# 005743-001.net
KiCad netlist of a schematic drawn in EAGLE
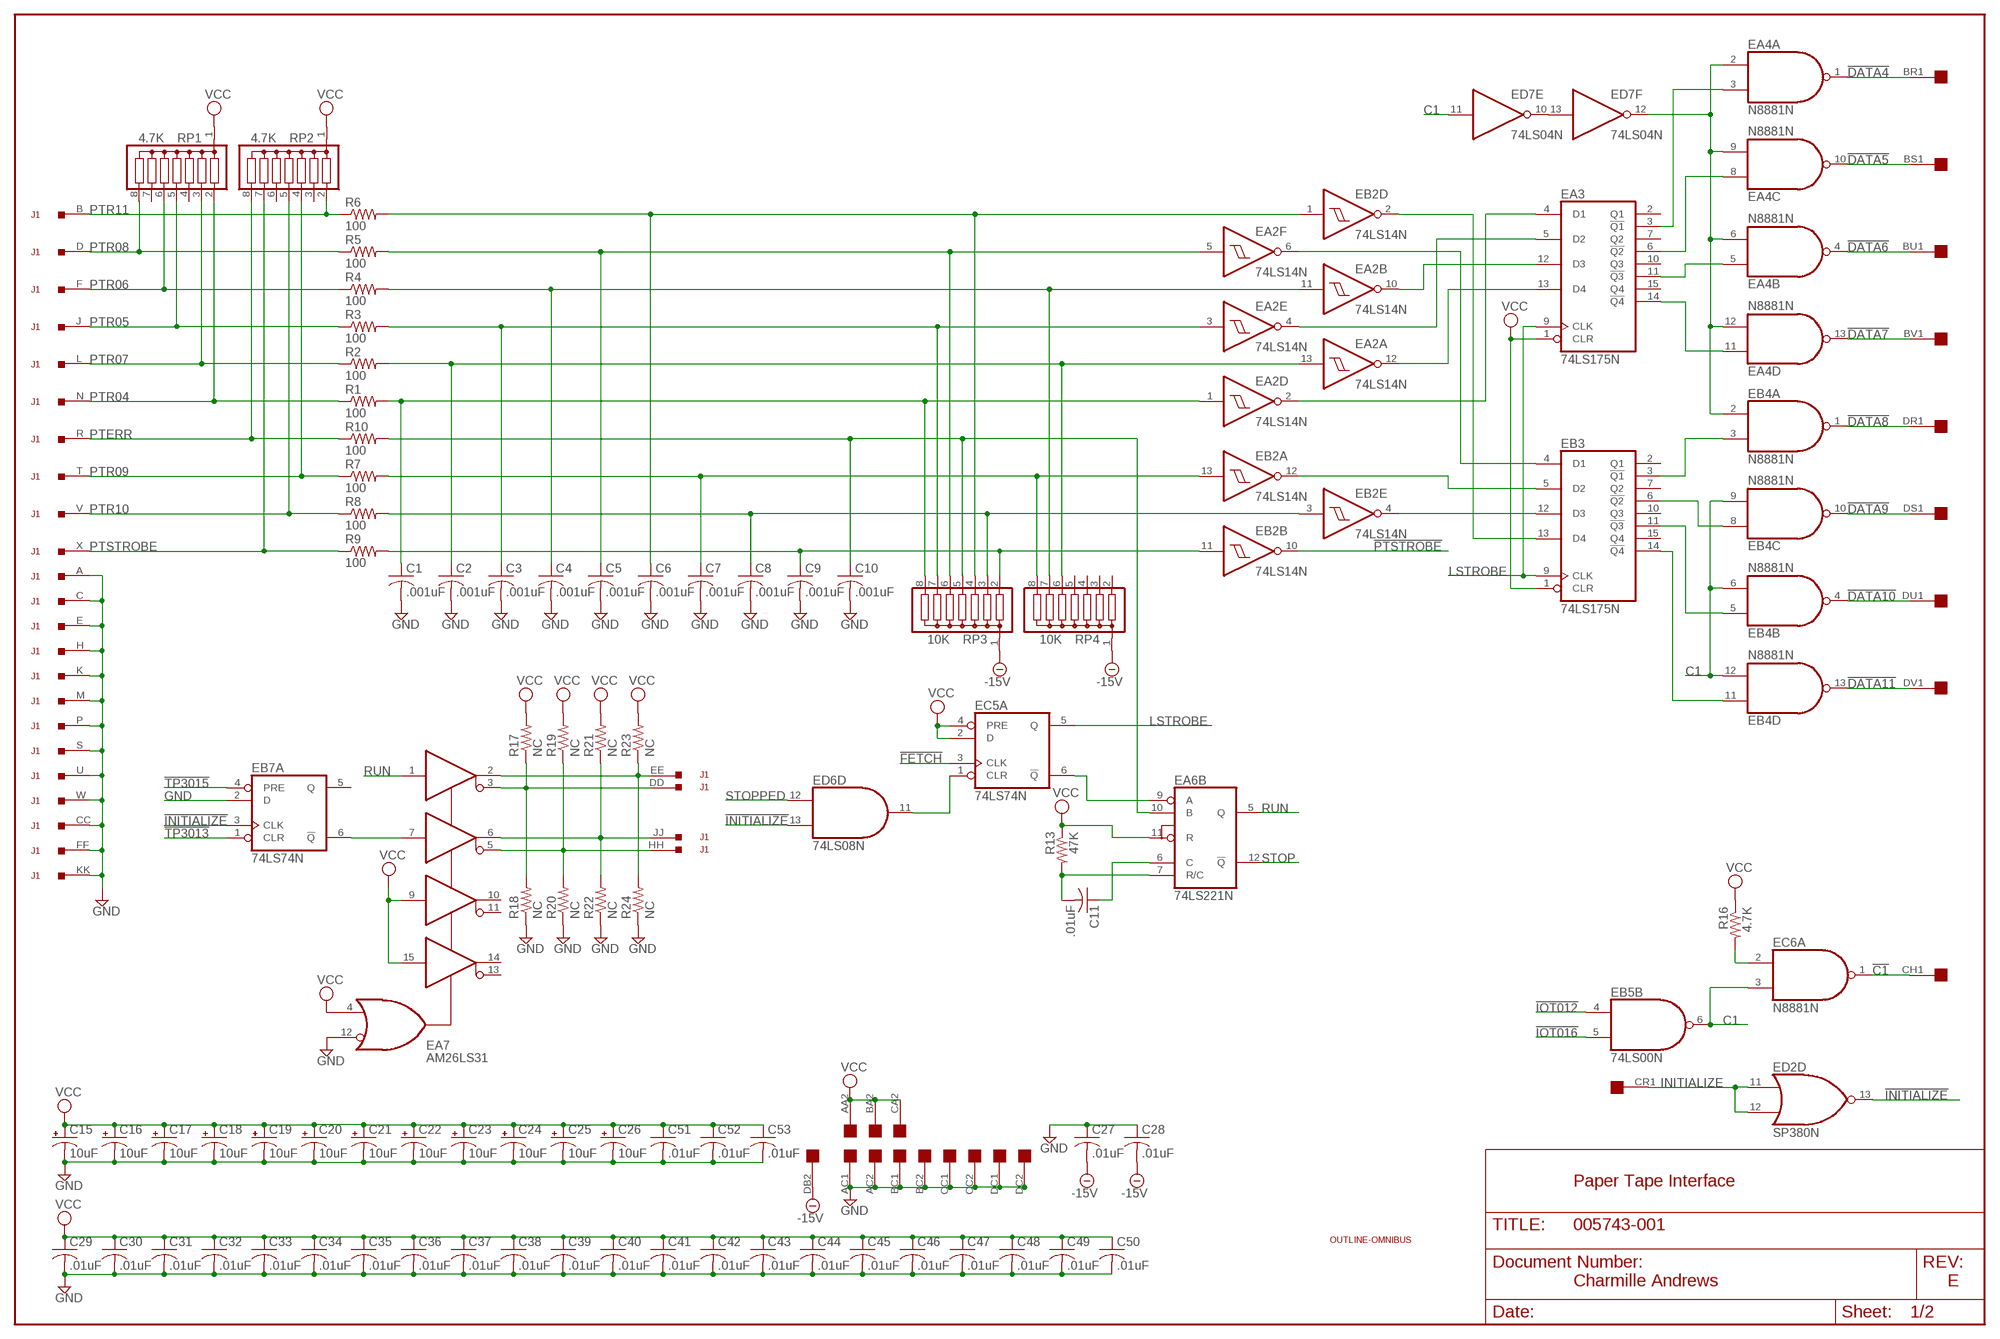
[diagram p0: schematic, sheet 1]
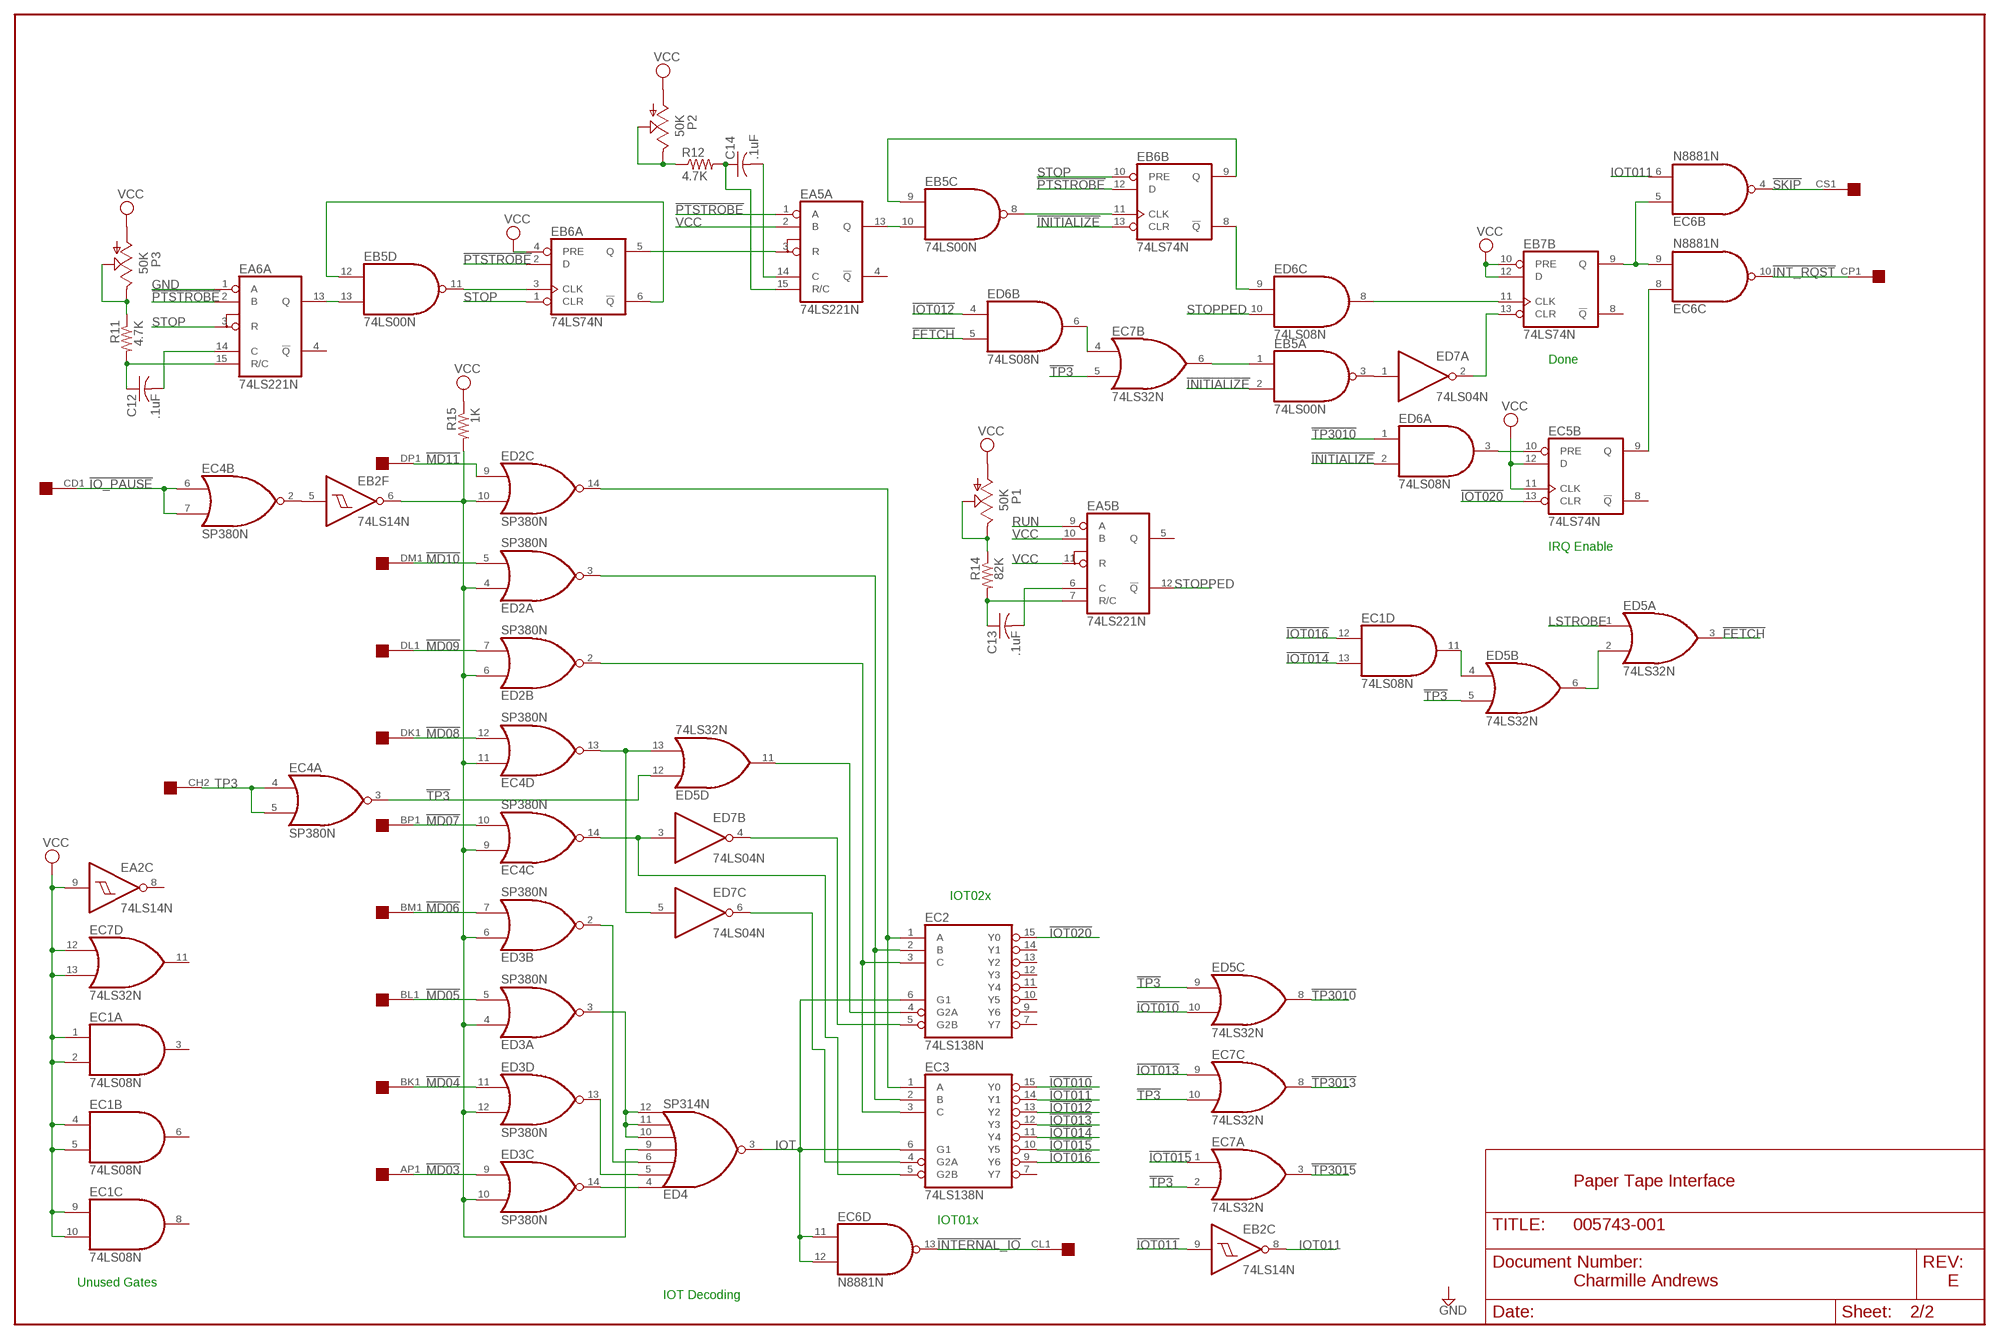
[diagram p1: schematic, sheet 2]

(export (version "E")
  (design (tool "Eeschema 10.0.6"))
  (components
    (comp (ref "C12")
      (value ".1uF")
      (footprint "eagle-import:C150-054X183")
      (libsource (lib "eagle-import") (part "C-US150-054X183"))
    )
    (comp (ref "C13")
      (value ".1uF")
      (footprint "eagle-import:C150-054X183")
      (libsource (lib "eagle-import") (part "C-US150-054X183"))
    )
    (comp (ref "C14")
      (value ".1uF")
      (footprint "eagle-import:C150-054X183")
      (libsource (lib "eagle-import") (part "C-US150-054X183"))
    )
    (comp (ref "EA2")
      (value "74LS14N")
      (footprint "eagle-import:DIL14")
      (libsource (lib "eagle-import") (part "7414NLS"))
    )
    (comp (ref "EA5")
      (value "74LS221N")
      (footprint "eagle-import:DIL16")
      (libsource (lib "eagle-import") (part "74221NLS"))
    )
    (comp (ref "EA6")
      (value "74LS221N")
      (footprint "eagle-import:DIL16")
      (libsource (lib "eagle-import") (part "74221NLS"))
    )
    (comp (ref "EB2")
      (value "74LS14N")
      (footprint "eagle-import:DIL14")
      (libsource (lib "eagle-import") (part "7414NLS"))
    )
    (comp (ref "EB5")
      (value "74LS00N")
      (footprint "eagle-import:DIL14")
      (libsource (lib "eagle-import") (part "7400NLS"))
    )
    (comp (ref "EB6")
      (value "74LS74N")
      (footprint "eagle-import:DIL14")
      (libsource (lib "eagle-import") (part "7474NLS"))
    )
    (comp (ref "EB7")
      (value "74LS74N")
      (footprint "eagle-import:DIL14")
      (libsource (lib "eagle-import") (part "7474NLS"))
    )
    (comp (ref "EC1")
      (value "74LS08N")
      (footprint "eagle-import:DIL14")
      (libsource (lib "eagle-import") (part "7408NLS"))
    )
    (comp (ref "EC2")
      (value "74LS138N")
      (footprint "eagle-import:DIL16")
      (libsource (lib "eagle-import") (part "74138NLS"))
    )
    (comp (ref "EC3")
      (value "74LS138N")
      (footprint "eagle-import:DIL16")
      (libsource (lib "eagle-import") (part "74138NLS"))
    )
    (comp (ref "EC4")
      (value "SP380N")
      (footprint "eagle-import:DIL14")
      (libsource (lib "eagle-import") (part "SP380N"))
    )
    (comp (ref "EC5")
      (value "74LS74N")
      (footprint "eagle-import:DIL14")
      (libsource (lib "eagle-import") (part "7474NLS"))
    )
    (comp (ref "EC6")
      (value "N8881N")
      (footprint "eagle-import:DIL14")
      (libsource (lib "eagle-import") (part "N8881N"))
    )
    (comp (ref "EC7")
      (value "74LS32N")
      (footprint "eagle-import:DIL14")
      (libsource (lib "eagle-import") (part "7432NLS"))
    )
    (comp (ref "ED2")
      (value "SP380N")
      (footprint "eagle-import:DIL14")
      (libsource (lib "eagle-import") (part "SP380N"))
    )
    (comp (ref "ED3")
      (value "SP380N")
      (footprint "eagle-import:DIL14")
      (libsource (lib "eagle-import") (part "SP380N"))
    )
    (comp (ref "ED4")
      (value "SP314N")
      (footprint "eagle-import:DIL14")
      (libsource (lib "eagle-import") (part "SP314N"))
    )
    (comp (ref "ED5")
      (value "74LS32N")
      (footprint "eagle-import:DIL14")
      (libsource (lib "eagle-import") (part "7432NLS"))
    )
    (comp (ref "ED6")
      (value "74LS08N")
      (footprint "eagle-import:DIL14")
      (libsource (lib "eagle-import") (part "7408NLS"))
    )
    (comp (ref "ED7")
      (value "74LS04N")
      (footprint "eagle-import:DIL14")
      (libsource (lib "eagle-import") (part "7404NLS"))
    )
    (comp (ref "P1")
      (value "50K")
      (footprint "eagle-import:SP19L")
      (libsource (lib "eagle-import") (part "TRIM_US-S43P"))
    )
    (comp (ref "P2")
      (value "50K")
      (footprint "eagle-import:SP19L")
      (libsource (lib "eagle-import") (part "TRIM_US-S43P"))
    )
    (comp (ref "P3")
      (value "50K")
      (footprint "eagle-import:SP19L")
      (libsource (lib "eagle-import") (part "TRIM_US-S43P"))
    )
    (comp (ref "R11")
      (value "4.7K")
      (footprint "eagle-import:0207_12")
      (libsource (lib "eagle-import") (part "R-US_0207/12"))
    )
    (comp (ref "R12")
      (value "4.7K")
      (footprint "eagle-import:0207_12")
      (libsource (lib "eagle-import") (part "R-US_0207/12"))
    )
    (comp (ref "R14")
      (value "82K")
      (footprint "eagle-import:0207_12")
      (libsource (lib "eagle-import") (part "R-US_0207/12"))
    )
    (comp (ref "R15")
      (value "1K")
      (footprint "eagle-import:0207_12")
      (libsource (lib "eagle-import") (part "R-US_0207/12"))
    )
    (comp (ref "U$2")
      (value "QUAD")
      (footprint "eagle-import:EDGE-CON8")
      (libsource (lib "eagle-import") (part "QUAD"))
    )
    (comp (ref "C1")
      (value ".001uF")
      (footprint "eagle-import:C050-025X075")
      (libsource (lib "eagle-import") (part "C-US050-025X075"))
    )
    (comp (ref "C2")
      (value ".001uF")
      (footprint "eagle-import:C050-025X075")
      (libsource (lib "eagle-import") (part "C-US050-025X075"))
    )
    (comp (ref "C3")
      (value ".001uF")
      (footprint "eagle-import:C050-025X075")
      (libsource (lib "eagle-import") (part "C-US050-025X075"))
    )
    (comp (ref "C4")
      (value ".001uF")
      (footprint "eagle-import:C050-025X075")
      (libsource (lib "eagle-import") (part "C-US050-025X075"))
    )
    (comp (ref "C5")
      (value ".001uF")
      (footprint "eagle-import:C050-025X075")
      (libsource (lib "eagle-import") (part "C-US050-025X075"))
    )
    (comp (ref "C6")
      (value ".001uF")
      (footprint "eagle-import:C050-025X075")
      (libsource (lib "eagle-import") (part "C-US050-025X075"))
    )
    (comp (ref "C7")
      (value ".001uF")
      (footprint "eagle-import:C050-025X075")
      (libsource (lib "eagle-import") (part "C-US050-025X075"))
    )
    (comp (ref "C8")
      (value ".001uF")
      (footprint "eagle-import:C050-025X075")
      (libsource (lib "eagle-import") (part "C-US050-025X075"))
    )
    (comp (ref "C9")
      (value ".001uF")
      (footprint "eagle-import:C050-025X075")
      (libsource (lib "eagle-import") (part "C-US050-025X075"))
    )
    (comp (ref "C10")
      (value ".001uF")
      (footprint "eagle-import:C050-025X075")
      (libsource (lib "eagle-import") (part "C-US050-025X075"))
    )
    (comp (ref "C11")
      (value ".01uF")
      (footprint "eagle-import:C050-025X075")
      (libsource (lib "eagle-import") (part "C-US050-025X075"))
    )
    (comp (ref "C15")
      (value "10uF")
      (footprint "eagle-import:E15-5")
      (libsource (lib "eagle-import") (part "CPOL-USE15-5AXIAL"))
    )
    (comp (ref "C16")
      (value "10uF")
      (footprint "eagle-import:E15-5")
      (libsource (lib "eagle-import") (part "rcl_CPOL-USE15-5AXIAL"))
    )
    (comp (ref "C17")
      (value "10uF")
      (footprint "eagle-import:E15-5")
      (libsource (lib "eagle-import") (part "rcl_CPOL-USE15-5AXIAL"))
    )
    (comp (ref "C18")
      (value "10uF")
      (footprint "eagle-import:E15-5")
      (libsource (lib "eagle-import") (part "CPOL-USE15-5AXIAL"))
    )
    (comp (ref "C19")
      (value "10uF")
      (footprint "eagle-import:E15-5")
      (libsource (lib "eagle-import") (part "rcl_CPOL-USE15-5AXIAL"))
    )
    (comp (ref "C20")
      (value "10uF")
      (footprint "eagle-import:E15-5")
      (libsource (lib "eagle-import") (part "CPOL-USE15-5AXIAL"))
    )
    (comp (ref "C21")
      (value "10uF")
      (footprint "eagle-import:E15-5")
      (libsource (lib "eagle-import") (part "CPOL-USE15-5AXIAL"))
    )
    (comp (ref "C22")
      (value "10uF")
      (footprint "eagle-import:E15-5")
      (libsource (lib "eagle-import") (part "CPOL-USE15-5AXIAL"))
    )
    (comp (ref "C23")
      (value "10uF")
      (footprint "eagle-import:E15-5")
      (libsource (lib "eagle-import") (part "rcl_CPOL-USE15-5AXIAL"))
    )
    (comp (ref "C24")
      (value "10uF")
      (footprint "eagle-import:E15-5")
      (libsource (lib "eagle-import") (part "rcl_CPOL-USE15-5AXIAL"))
    )
    (comp (ref "C25")
      (value "10uF")
      (footprint "eagle-import:E15-5")
      (libsource (lib "eagle-import") (part "rcl_CPOL-USE15-5AXIAL"))
    )
    (comp (ref "C26")
      (value "10uF")
      (footprint "eagle-import:E15-5")
      (libsource (lib "eagle-import") (part "rcl_CPOL-USE15-5AXIAL"))
    )
    (comp (ref "C27")
      (value ".01uF")
      (footprint "eagle-import:C050-025X075")
      (libsource (lib "eagle-import") (part "C-US050-025X075"))
    )
    (comp (ref "C28")
      (value ".01uF")
      (footprint "eagle-import:C050-025X075")
      (libsource (lib "eagle-import") (part "C-US050-025X075"))
    )
    (comp (ref "C29")
      (value ".01uF")
      (footprint "eagle-import:C050-025X075")
      (libsource (lib "eagle-import") (part "C-US050-025X075"))
    )
    (comp (ref "C30")
      (value ".01uF")
      (footprint "eagle-import:C050-025X075")
      (libsource (lib "eagle-import") (part "C-US050-025X075"))
    )
    (comp (ref "C31")
      (value ".01uF")
      (footprint "eagle-import:C050-025X075")
      (libsource (lib "eagle-import") (part "C-US050-025X075"))
    )
    (comp (ref "C32")
      (value ".01uF")
      (footprint "eagle-import:C050-025X075")
      (libsource (lib "eagle-import") (part "C-US050-025X075"))
    )
    (comp (ref "C33")
      (value ".01uF")
      (footprint "eagle-import:C050-025X075")
      (libsource (lib "eagle-import") (part "C-US050-025X075"))
    )
    (comp (ref "C34")
      (value ".01uF")
      (footprint "eagle-import:C050-025X075")
      (libsource (lib "eagle-import") (part "C-US050-025X075"))
    )
    (comp (ref "C35")
      (value ".01uF")
      (footprint "eagle-import:C050-025X075")
      (libsource (lib "eagle-import") (part "C-US050-025X075"))
    )
    (comp (ref "C36")
      (value ".01uF")
      (footprint "eagle-import:C050-025X075")
      (libsource (lib "eagle-import") (part "C-US050-025X075"))
    )
    (comp (ref "C37")
      (value ".01uF")
      (footprint "eagle-import:C050-025X075")
      (libsource (lib "eagle-import") (part "C-US050-025X075"))
    )
    (comp (ref "C38")
      (value ".01uF")
      (footprint "eagle-import:C050-025X075")
      (libsource (lib "eagle-import") (part "C-US050-025X075"))
    )
    (comp (ref "C39")
      (value ".01uF")
      (footprint "eagle-import:C050-025X075")
      (libsource (lib "eagle-import") (part "C-US050-025X075"))
    )
    (comp (ref "C40")
      (value ".01uF")
      (footprint "eagle-import:C050-025X075")
      (libsource (lib "eagle-import") (part "C-US050-025X075"))
    )
    (comp (ref "C41")
      (value ".01uF")
      (footprint "eagle-import:C050-025X075")
      (libsource (lib "eagle-import") (part "C-US050-025X075"))
    )
    (comp (ref "C42")
      (value ".01uF")
      (footprint "eagle-import:C050-025X075")
      (libsource (lib "eagle-import") (part "C-US050-025X075"))
    )
    (comp (ref "C43")
      (value ".01uF")
      (footprint "eagle-import:C050-025X075")
      (libsource (lib "eagle-import") (part "C-US050-025X075"))
    )
    (comp (ref "C44")
      (value ".01uF")
      (footprint "eagle-import:C050-025X075")
      (libsource (lib "eagle-import") (part "C-US050-025X075"))
    )
    (comp (ref "C45")
      (value ".01uF")
      (footprint "eagle-import:C050-025X075")
      (libsource (lib "eagle-import") (part "C-US050-025X075"))
    )
    (comp (ref "C46")
      (value ".01uF")
      (footprint "eagle-import:C050-025X075")
      (libsource (lib "eagle-import") (part "C-US050-025X075"))
    )
    (comp (ref "C47")
      (value ".01uF")
      (footprint "eagle-import:C050-025X075")
      (libsource (lib "eagle-import") (part "C-US050-025X075"))
    )
    (comp (ref "C48")
      (value ".01uF")
      (footprint "eagle-import:C050-025X075")
      (libsource (lib "eagle-import") (part "C-US050-025X075"))
    )
    (comp (ref "C49")
      (value ".01uF")
      (footprint "eagle-import:C050-025X075")
      (libsource (lib "eagle-import") (part "C-US050-025X075"))
    )
    (comp (ref "C50")
      (value ".01uF")
      (footprint "eagle-import:C050-025X075")
      (libsource (lib "eagle-import") (part "C-US050-025X075"))
    )
    (comp (ref "C51")
      (value ".01uF")
      (footprint "eagle-import:C050-025X075")
      (libsource (lib "eagle-import") (part "C-US050-025X075"))
    )
    (comp (ref "C52")
      (value ".01uF")
      (footprint "eagle-import:C050-025X075")
      (libsource (lib "eagle-import") (part "C-US050-025X075"))
    )
    (comp (ref "C53")
      (value ".01uF")
      (footprint "eagle-import:C050-025X075")
      (libsource (lib "eagle-import") (part "C-US050-025X075"))
    )
    (comp (ref "EA3")
      (value "74LS175N")
      (footprint "eagle-import:DIL16")
      (libsource (lib "eagle-import") (part "74175NLS"))
    )
    (comp (ref "EA4")
      (value "N8881N")
      (footprint "eagle-import:DIL14")
      (libsource (lib "eagle-import") (part "N8881N"))
    )
    (comp (ref "EA7")
      (value "AM26LS31")
      (footprint "eagle-import:DIL16")
      (libsource (lib "eagle-import") (part "AM26LS31"))
    )
    (comp (ref "EB3")
      (value "74LS175N")
      (footprint "eagle-import:DIL16")
      (libsource (lib "eagle-import") (part "74175NLS"))
    )
    (comp (ref "EB4")
      (value "N8881N")
      (footprint "eagle-import:DIL14")
      (libsource (lib "eagle-import") (part "N8881N"))
    )
    (comp (ref "J1")
      (value "DEC40PINSH")
      (footprint "eagle-import:DEC40PINH")
      (libsource (lib "eagle-import") (part "DEC40PINSH"))
    )
    (comp (ref "R1")
      (value "100")
      (footprint "eagle-import:0207_12")
      (libsource (lib "eagle-import") (part "R-US_0207/12"))
    )
    (comp (ref "R2")
      (value "100")
      (footprint "eagle-import:0207_12")
      (libsource (lib "eagle-import") (part "R-US_0207/12"))
    )
    (comp (ref "R3")
      (value "100")
      (footprint "eagle-import:0207_12")
      (libsource (lib "eagle-import") (part "R-US_0207/12"))
    )
    (comp (ref "R4")
      (value "100")
      (footprint "eagle-import:0207_12")
      (libsource (lib "eagle-import") (part "R-US_0207/12"))
    )
    (comp (ref "R5")
      (value "100")
      (footprint "eagle-import:0207_12")
      (libsource (lib "eagle-import") (part "R-US_0207/12"))
    )
    (comp (ref "R6")
      (value "100")
      (footprint "eagle-import:0207_12")
      (libsource (lib "eagle-import") (part "R-US_0207/12"))
    )
    (comp (ref "R7")
      (value "100")
      (footprint "eagle-import:0207_12")
      (libsource (lib "eagle-import") (part "R-US_0207/12"))
    )
    (comp (ref "R8")
      (value "100")
      (footprint "eagle-import:0207_12")
      (libsource (lib "eagle-import") (part "R-US_0207/12"))
    )
    (comp (ref "R9")
      (value "100")
      (footprint "eagle-import:0207_12")
      (libsource (lib "eagle-import") (part "R-US_0207/12"))
    )
    (comp (ref "R10")
      (value "100")
      (footprint "eagle-import:0207_12")
      (libsource (lib "eagle-import") (part "R-US_0207/12"))
    )
    (comp (ref "R13")
      (value "47K")
      (footprint "eagle-import:0207_12")
      (libsource (lib "eagle-import") (part "R-US_0207/12"))
    )
    (comp (ref "R16")
      (value "4.7K")
      (footprint "eagle-import:0207_12")
      (libsource (lib "eagle-import") (part "R-US_0207/12"))
    )
    (comp (ref "R17")
      (value "NC")
      (footprint "eagle-import:0207_12")
      (libsource (lib "eagle-import") (part "R-US_0207/12"))
    )
    (comp (ref "R18")
      (value "NC")
      (footprint "eagle-import:0207_12")
      (libsource (lib "eagle-import") (part "R-US_0207/12"))
    )
    (comp (ref "R19")
      (value "NC")
      (footprint "eagle-import:0207_12")
      (libsource (lib "eagle-import") (part "R-US_0207/12"))
    )
    (comp (ref "R20")
      (value "NC")
      (footprint "eagle-import:0207_12")
      (libsource (lib "eagle-import") (part "R-US_0207/12"))
    )
    (comp (ref "R21")
      (value "NC")
      (footprint "eagle-import:0207_12")
      (libsource (lib "eagle-import") (part "R-US_0207/12"))
    )
    (comp (ref "R22")
      (value "NC")
      (footprint "eagle-import:0207_12")
      (libsource (lib "eagle-import") (part "R-US_0207/12"))
    )
    (comp (ref "R23")
      (value "NC")
      (footprint "eagle-import:0207_12")
      (libsource (lib "eagle-import") (part "R-US_0207/12"))
    )
    (comp (ref "R24")
      (value "NC")
      (footprint "eagle-import:0207_12")
      (libsource (lib "eagle-import") (part "R-US_0207/12"))
    )
    (comp (ref "RP1")
      (value "4.7K")
      (footprint "eagle-import:SIL8")
      (libsource (lib "eagle-import") (part "G07R"))
    )
    (comp (ref "RP2")
      (value "4.7K")
      (footprint "eagle-import:SIL8")
      (libsource (lib "eagle-import") (part "G07R"))
    )
    (comp (ref "RP3")
      (value "10K")
      (footprint "eagle-import:SIL8")
      (libsource (lib "eagle-import") (part "G07R"))
    )
    (comp (ref "RP4")
      (value "10K")
      (footprint "eagle-import:SIL8")
      (libsource (lib "eagle-import") (part "G07R"))
    )
    (comp (ref "U$1")
      (value "OUTLINE-OMNIBUS")
      (footprint "eagle-import:OMNIBUS")
      (libsource (lib "eagle-import") (part "OUTLINE-OMNIBUS"))
    )
  )
  (nets
    (net (code "1") (name "-15V") (class "Default")
      (node (ref "C27") (pin "2") (pinfunction "2_2") (pintype "passive"))
      (node (ref "C28") (pin "2") (pinfunction "2_2") (pintype "passive"))
      (node (ref "RP3") (pin "1") (pinfunction "1_1") (pintype "passive"))
      (node (ref "RP4") (pin "1") (pinfunction "1_1") (pintype "passive"))
      (node (ref "U$2") (pin "DB2") (pinfunction "1_DB2") (pintype "bidirectional"))
    )
    (net (code "2") (name "C1") (class "Default")
      (node (ref "EB4") (pin "12") (pinfunction "I1_12") (pintype "input"))
      (node (ref "EB4") (pin "6") (pinfunction "I1_6") (pintype "input"))
      (node (ref "EB4") (pin "9") (pinfunction "I1_9") (pintype "input"))
      (node (ref "EB5") (pin "6") (pinfunction "O_6") (pintype "output"))
      (node (ref "EC6") (pin "3") (pinfunction "I1_3") (pintype "input"))
      (node (ref "ED7") (pin "11") (pinfunction "I_11") (pintype "input"))
    )
    (net (code "3") (name "GND") (class "Default")
      (node (ref "C1") (pin "2") (pinfunction "2_2") (pintype "passive"))
      (node (ref "C10") (pin "2") (pinfunction "2_2") (pintype "passive"))
      (node (ref "C15") (pin "-") (pinfunction "-_-") (pintype "passive"))
      (node (ref "C16") (pin "-") (pinfunction "-_-") (pintype "passive"))
      (node (ref "C17") (pin "-") (pinfunction "-_-") (pintype "passive"))
      (node (ref "C18") (pin "-") (pinfunction "-_-") (pintype "passive"))
      (node (ref "C19") (pin "-") (pinfunction "-_-") (pintype "passive"))
      (node (ref "C2") (pin "2") (pinfunction "2_2") (pintype "passive"))
      (node (ref "C20") (pin "-") (pinfunction "-_-") (pintype "passive"))
      (node (ref "C21") (pin "-") (pinfunction "-_-") (pintype "passive"))
      (node (ref "C22") (pin "-") (pinfunction "-_-") (pintype "passive"))
      (node (ref "C23") (pin "-") (pinfunction "-_-") (pintype "passive"))
      (node (ref "C24") (pin "-") (pinfunction "-_-") (pintype "passive"))
      (node (ref "C25") (pin "-") (pinfunction "-_-") (pintype "passive"))
      (node (ref "C26") (pin "-") (pinfunction "-_-") (pintype "passive"))
      (node (ref "C27") (pin "1") (pinfunction "1_1") (pintype "passive"))
      (node (ref "C28") (pin "1") (pinfunction "1_1") (pintype "passive"))
      (node (ref "C29") (pin "2") (pinfunction "2_2") (pintype "passive"))
      (node (ref "C3") (pin "2") (pinfunction "2_2") (pintype "passive"))
      (node (ref "C30") (pin "2") (pinfunction "2_2") (pintype "passive"))
      (node (ref "C31") (pin "2") (pinfunction "2_2") (pintype "passive"))
      (node (ref "C32") (pin "2") (pinfunction "2_2") (pintype "passive"))
      (node (ref "C33") (pin "2") (pinfunction "2_2") (pintype "passive"))
      (node (ref "C34") (pin "2") (pinfunction "2_2") (pintype "passive"))
      (node (ref "C35") (pin "2") (pinfunction "2_2") (pintype "passive"))
      (node (ref "C36") (pin "2") (pinfunction "2_2") (pintype "passive"))
      (node (ref "C37") (pin "2") (pinfunction "2_2") (pintype "passive"))
      (node (ref "C38") (pin "2") (pinfunction "2_2") (pintype "passive"))
      (node (ref "C39") (pin "2") (pinfunction "2_2") (pintype "passive"))
      (node (ref "C4") (pin "2") (pinfunction "2_2") (pintype "passive"))
      (node (ref "C40") (pin "2") (pinfunction "2_2") (pintype "passive"))
      (node (ref "C41") (pin "2") (pinfunction "2_2") (pintype "passive"))
      (node (ref "C42") (pin "2") (pinfunction "2_2") (pintype "passive"))
      (node (ref "C43") (pin "2") (pinfunction "2_2") (pintype "passive"))
      (node (ref "C44") (pin "2") (pinfunction "2_2") (pintype "passive"))
      (node (ref "C45") (pin "2") (pinfunction "2_2") (pintype "passive"))
      (node (ref "C46") (pin "2") (pinfunction "2_2") (pintype "passive"))
      (node (ref "C47") (pin "2") (pinfunction "2_2") (pintype "passive"))
      (node (ref "C48") (pin "2") (pinfunction "2_2") (pintype "passive"))
      (node (ref "C49") (pin "2") (pinfunction "2_2") (pintype "passive"))
      (node (ref "C5") (pin "2") (pinfunction "2_2") (pintype "passive"))
      (node (ref "C50") (pin "2") (pinfunction "2_2") (pintype "passive"))
      (node (ref "C51") (pin "2") (pinfunction "2_2") (pintype "passive"))
      (node (ref "C52") (pin "2") (pinfunction "2_2") (pintype "passive"))
      (node (ref "C53") (pin "2") (pinfunction "2_2") (pintype "passive"))
      (node (ref "C6") (pin "2") (pinfunction "2_2") (pintype "passive"))
      (node (ref "C7") (pin "2") (pinfunction "2_2") (pintype "passive"))
      (node (ref "C8") (pin "2") (pinfunction "2_2") (pintype "passive"))
      (node (ref "C9") (pin "2") (pinfunction "2_2") (pintype "passive"))
      (node (ref "EA6") (pin "1") (pinfunction "A_1") (pintype "input"))
      (node (ref "EA7") (pin "12") (pinfunction "~{G}_12") (pintype "input"))
      (node (ref "EB7") (pin "2") (pinfunction "D_2") (pintype "input"))
      (node (ref "J1") (pin "A") (pinfunction "P$2_A") (pintype "passive"))
      (node (ref "J1") (pin "C") (pinfunction "P$2_C") (pintype "passive"))
      (node (ref "J1") (pin "CC") (pinfunction "P$2_CC") (pintype "passive"))
      (node (ref "J1") (pin "E") (pinfunction "P$2_E") (pintype "passive"))
      (node (ref "J1") (pin "FF") (pinfunction "P$2_FF") (pintype "passive"))
      (node (ref "J1") (pin "H") (pinfunction "P$2_H") (pintype "passive"))
      (node (ref "J1") (pin "K") (pinfunction "P$2_K") (pintype "passive"))
      (node (ref "J1") (pin "KK") (pinfunction "P$2_KK") (pintype "passive"))
      (node (ref "J1") (pin "M") (pinfunction "P$2_M") (pintype "passive"))
      (node (ref "J1") (pin "P") (pinfunction "P$2_P") (pintype "passive"))
      (node (ref "J1") (pin "S") (pinfunction "P$2_S") (pintype "passive"))
      (node (ref "J1") (pin "U") (pinfunction "P$2_U") (pintype "passive"))
      (node (ref "J1") (pin "W") (pinfunction "P$2_W") (pintype "passive"))
      (node (ref "R18") (pin "1") (pinfunction "1_1") (pintype "passive"))
      (node (ref "R20") (pin "1") (pinfunction "1_1") (pintype "passive"))
      (node (ref "R22") (pin "1") (pinfunction "1_1") (pintype "passive"))
      (node (ref "R24") (pin "1") (pinfunction "1_1") (pintype "passive"))
      (node (ref "U$2") (pin "AC1") (pinfunction "1_AC1") (pintype "bidirectional"))
      (node (ref "U$2") (pin "AC2") (pinfunction "1_AC2") (pintype "bidirectional"))
      (node (ref "U$2") (pin "BC1") (pinfunction "1_BC1") (pintype "bidirectional"))
      (node (ref "U$2") (pin "BC2") (pinfunction "1_BC2") (pintype "bidirectional"))
      (node (ref "U$2") (pin "CC1") (pinfunction "1_CC1") (pintype "bidirectional"))
      (node (ref "U$2") (pin "CC2") (pinfunction "1_CC2") (pintype "bidirectional"))
      (node (ref "U$2") (pin "DC1") (pinfunction "1_DC1") (pintype "bidirectional"))
      (node (ref "U$2") (pin "DC2") (pinfunction "1_DC2") (pintype "bidirectional"))
    )
    (net (code "4") (name "INITIALIZE") (class "Default")
      (node (ref "ED2") (pin "11") (pinfunction "I0_11") (pintype "input"))
      (node (ref "ED2") (pin "12") (pinfunction "I1_12") (pintype "input"))
      (node (ref "U$2") (pin "CR1") (pinfunction "1_CR1") (pintype "bidirectional"))
    )
    (net (code "5") (name "IOT") (class "Default")
      (node (ref "EC2") (pin "6") (pinfunction "G1_6") (pintype "input"))
      (node (ref "EC3") (pin "6") (pinfunction "G1_6") (pintype "input"))
      (node (ref "EC6") (pin "11") (pinfunction "I0_11") (pintype "input"))
      (node (ref "EC6") (pin "12") (pinfunction "I1_12") (pintype "input"))
      (node (ref "ED4") (pin "3") (pinfunction "O_3") (pintype "output"))
    )
    (net (code "6") (name "IOT011") (class "Default")
      (node (ref "EB2") (pin "8") (pinfunction "O_8") (pintype "output"))
      (node (ref "EC6") (pin "6") (pinfunction "I1_6") (pintype "input"))
    )
    (net (code "7") (name "LSTROBE") (class "Default")
      (node (ref "EA3") (pin "9") (pinfunction "CLK_9") (pintype "input"))
      (node (ref "EB3") (pin "9") (pinfunction "CLK_9") (pintype "input"))
      (node (ref "EC5") (pin "5") (pinfunction "Q_5") (pintype "output"))
      (node (ref "ED5") (pin "1") (pinfunction "I0_1") (pintype "input"))
    )
    (net (code "8") (name "Net-(EA2A-I)") (class "Default")
      (node (ref "C2") (pin "1") (pinfunction "1_1") (pintype "passive"))
      (node (ref "EA2") (pin "13") (pinfunction "I_13") (pintype "input"))
      (node (ref "R2") (pin "2") (pinfunction "2_2") (pintype "passive"))
      (node (ref "RP4") (pin "6") (pinfunction "6_6") (pintype "passive"))
    )
    (net (code "9") (name "Net-(EA2A-O)") (class "Default")
      (node (ref "EA2") (pin "12") (pinfunction "O_12") (pintype "output"))
      (node (ref "EA3") (pin "13") (pinfunction "D4_13") (pintype "input"))
    )
    (net (code "10") (name "Net-(EA2B-I)") (class "Default")
      (node (ref "C4") (pin "1") (pinfunction "1_1") (pintype "passive"))
      (node (ref "EA2") (pin "11") (pinfunction "I_11") (pintype "input"))
      (node (ref "R4") (pin "2") (pinfunction "2_2") (pintype "passive"))
      (node (ref "RP4") (pin "7") (pinfunction "7_7") (pintype "passive"))
    )
    (net (code "11") (name "Net-(EA2B-O)") (class "Default")
      (node (ref "EA2") (pin "10") (pinfunction "O_10") (pintype "output"))
      (node (ref "EA3") (pin "12") (pinfunction "D3_12") (pintype "input"))
    )
    (net (code "12") (name "Net-(EA2D-I)") (class "Default")
      (node (ref "C1") (pin "1") (pinfunction "1_1") (pintype "passive"))
      (node (ref "EA2") (pin "1") (pinfunction "I_1") (pintype "input"))
      (node (ref "R1") (pin "2") (pinfunction "2_2") (pintype "passive"))
      (node (ref "RP3") (pin "8") (pinfunction "8_8") (pintype "passive"))
    )
    (net (code "13") (name "Net-(EA2D-O)") (class "Default")
      (node (ref "EA2") (pin "2") (pinfunction "O_2") (pintype "output"))
      (node (ref "EA3") (pin "4") (pinfunction "D1_4") (pintype "input"))
    )
    (net (code "14") (name "Net-(EA2E-I)") (class "Default")
      (node (ref "C3") (pin "1") (pinfunction "1_1") (pintype "passive"))
      (node (ref "EA2") (pin "3") (pinfunction "I_3") (pintype "input"))
      (node (ref "R3") (pin "2") (pinfunction "2_2") (pintype "passive"))
      (node (ref "RP3") (pin "7") (pinfunction "7_7") (pintype "passive"))
    )
    (net (code "15") (name "Net-(EA2E-O)") (class "Default")
      (node (ref "EA2") (pin "4") (pinfunction "O_4") (pintype "output"))
      (node (ref "EA3") (pin "5") (pinfunction "D2_5") (pintype "input"))
    )
    (net (code "16") (name "Net-(EA2F-I)") (class "Default")
      (node (ref "C5") (pin "1") (pinfunction "1_1") (pintype "passive"))
      (node (ref "EA2") (pin "5") (pinfunction "I_5") (pintype "input"))
      (node (ref "R5") (pin "2") (pinfunction "2_2") (pintype "passive"))
      (node (ref "RP3") (pin "6") (pinfunction "6_6") (pintype "passive"))
    )
    (net (code "17") (name "Net-(EA2F-O)") (class "Default")
      (node (ref "EA2") (pin "6") (pinfunction "O_6") (pintype "output"))
      (node (ref "EB3") (pin "4") (pinfunction "D1_4") (pintype "input"))
    )
    (net (code "18") (name "Net-(EA3A-~{Q1})") (class "Default")
      (node (ref "EA3") (pin "3") (pinfunction "~{Q1}_3") (pintype "output"))
      (node (ref "EA4") (pin "3") (pinfunction "I1_3") (pintype "input"))
    )
    (net (code "19") (name "Net-(EA3A-~{Q2})") (class "Default")
      (node (ref "EA3") (pin "6") (pinfunction "~{Q2}_6") (pintype "output"))
      (node (ref "EA4") (pin "8") (pinfunction "I0_8") (pintype "input"))
    )
    (net (code "20") (name "Net-(EA3A-~{Q3})") (class "Default")
      (node (ref "EA3") (pin "11") (pinfunction "~{Q3}_11") (pintype "output"))
      (node (ref "EA4") (pin "5") (pinfunction "I0_5") (pintype "input"))
    )
    (net (code "21") (name "Net-(EA3A-~{Q4})") (class "Default")
      (node (ref "EA3") (pin "14") (pinfunction "~{Q4}_14") (pintype "output"))
      (node (ref "EA4") (pin "11") (pinfunction "I0_11") (pintype "input"))
    )
    (net (code "22") (name "Net-(EA4A-I0)") (class "Default")
      (node (ref "EA4") (pin "12") (pinfunction "I1_12") (pintype "input"))
      (node (ref "EA4") (pin "2") (pinfunction "I0_2") (pintype "input"))
      (node (ref "EA4") (pin "6") (pinfunction "I1_6") (pintype "input"))
      (node (ref "EA4") (pin "9") (pinfunction "I1_9") (pintype "input"))
      (node (ref "EB4") (pin "2") (pinfunction "I0_2") (pintype "input"))
      (node (ref "ED7") (pin "12") (pinfunction "O_12") (pintype "output"))
    )
    (net (code "23") (name "Net-(EA5A-C)") (class "Default")
      (node (ref "C14") (pin "2") (pinfunction "2_2") (pintype "passive"))
      (node (ref "EA5") (pin "14") (pinfunction "C_14") (pintype "input"))
    )
    (net (code "24") (name "Net-(EA5A-Q)") (class "Default")
      (node (ref "EA5") (pin "13") (pinfunction "Q_13") (pintype "output"))
      (node (ref "EB5") (pin "10") (pinfunction "I1_10") (pintype "input"))
    )
    (net (code "25") (name "Net-(EA5A-R)") (class "Default")
      (node (ref "EA5") (pin "3") (pinfunction "R_3") (pintype "input"))
      (node (ref "EB6") (pin "5") (pinfunction "Q_5") (pintype "output"))
    )
    (net (code "26") (name "Net-(EA5A-R{slash}C)") (class "Default")
      (node (ref "C14") (pin "1") (pinfunction "1_1") (pintype "passive"))
      (node (ref "EA5") (pin "15") (pinfunction "R/C_15") (pintype "input"))
      (node (ref "R12") (pin "2") (pinfunction "2_2") (pintype "passive"))
    )
    (net (code "27") (name "Net-(EA5B-C)") (class "Default")
      (node (ref "C13") (pin "2") (pinfunction "2_2") (pintype "passive"))
      (node (ref "EA5") (pin "6") (pinfunction "C_6") (pintype "input"))
    )
    (net (code "28") (name "Net-(EA5B-R{slash}C)") (class "Default")
      (node (ref "C13") (pin "1") (pinfunction "1_1") (pintype "passive"))
      (node (ref "EA5") (pin "7") (pinfunction "R/C_7") (pintype "input"))
      (node (ref "R14") (pin "2") (pinfunction "2_2") (pintype "passive"))
    )
    (net (code "29") (name "Net-(EA6A-C)") (class "Default")
      (node (ref "C12") (pin "2") (pinfunction "2_2") (pintype "passive"))
      (node (ref "EA6") (pin "14") (pinfunction "C_14") (pintype "input"))
    )
    (net (code "30") (name "Net-(EA6A-Q)") (class "Default")
      (node (ref "EA6") (pin "13") (pinfunction "Q_13") (pintype "output"))
      (node (ref "EB5") (pin "13") (pinfunction "I1_13") (pintype "input"))
    )
    (net (code "31") (name "Net-(EA6A-R{slash}C)") (class "Default")
      (node (ref "C12") (pin "1") (pinfunction "1_1") (pintype "passive"))
      (node (ref "EA6") (pin "15") (pinfunction "R/C_15") (pintype "input"))
      (node (ref "R11") (pin "2") (pinfunction "2_2") (pintype "passive"))
    )
    (net (code "32") (name "Net-(EA6B-A)") (class "Default")
      (node (ref "EA6") (pin "9") (pinfunction "A_9") (pintype "input"))
      (node (ref "EC5") (pin "6") (pinfunction "~{Q}_6") (pintype "output"))
    )
    (net (code "33") (name "Net-(EA6B-B)") (class "Default")
      (node (ref "C10") (pin "1") (pinfunction "1_1") (pintype "passive"))
      (node (ref "EA6") (pin "10") (pinfunction "B_10") (pintype "input"))
      (node (ref "R10") (pin "2") (pinfunction "2_2") (pintype "passive"))
      (node (ref "RP3") (pin "5") (pinfunction "5_5") (pintype "passive"))
    )
    (net (code "34") (name "Net-(EA6B-C)") (class "Default")
      (node (ref "C11") (pin "1") (pinfunction "1_1") (pintype "passive"))
      (node (ref "EA6") (pin "6") (pinfunction "C_6") (pintype "input"))
    )
    (net (code "35") (name "Net-(EA6B-R{slash}C)") (class "Default")
      (node (ref "C11") (pin "2") (pinfunction "2_2") (pintype "passive"))
      (node (ref "EA6") (pin "7") (pinfunction "R/C_7") (pintype "input"))
      (node (ref "R13") (pin "2") (pinfunction "2_2") (pintype "passive"))
    )
    (net (code "36") (name "Net-(EA7A-A2)") (class "Default")
      (node (ref "EA7") (pin "7") (pinfunction "A2_7") (pintype "input"))
      (node (ref "EB7") (pin "6") (pinfunction "~{Q}_6") (pintype "output"))
    )
    (net (code "37") (name "Net-(EA7A-Y1)") (class "Default")
      (node (ref "EA7") (pin "2") (pinfunction "Y1_2") (pintype "output"))
      (node (ref "J1") (pin "EE") (pinfunction "P$2_EE") (pintype "passive"))
      (node (ref "R23") (pin "1") (pinfunction "1_1") (pintype "passive"))
      (node (ref "R24") (pin "2") (pinfunction "2_2") (pintype "passive"))
    )
    (net (code "38") (name "Net-(EA7A-Y2)") (class "Default")
      (node (ref "EA7") (pin "6") (pinfunction "Y2_6") (pintype "output"))
      (node (ref "J1") (pin "JJ") (pinfunction "P$2_JJ") (pintype "passive"))
      (node (ref "R21") (pin "1") (pinfunction "1_1") (pintype "passive"))
      (node (ref "R22") (pin "2") (pinfunction "2_2") (pintype "passive"))
    )
    (net (code "39") (name "Net-(EA7A-Z1)") (class "Default")
      (node (ref "EA7") (pin "3") (pinfunction "Z1_3") (pintype "output"))
      (node (ref "J1") (pin "DD") (pinfunction "P$2_DD") (pintype "passive"))
      (node (ref "R17") (pin "1") (pinfunction "1_1") (pintype "passive"))
      (node (ref "R18") (pin "2") (pinfunction "2_2") (pintype "passive"))
    )
    (net (code "40") (name "Net-(EA7A-Z2)") (class "Default")
      (node (ref "EA7") (pin "5") (pinfunction "Z2_5") (pintype "output"))
      (node (ref "J1") (pin "HH") (pinfunction "P$2_HH") (pintype "passive"))
      (node (ref "R19") (pin "1") (pinfunction "1_1") (pintype "passive"))
      (node (ref "R20") (pin "2") (pinfunction "2_2") (pintype "passive"))
    )
    (net (code "41") (name "Net-(EB2A-I)") (class "Default")
      (node (ref "C7") (pin "1") (pinfunction "1_1") (pintype "passive"))
      (node (ref "EB2") (pin "13") (pinfunction "I_13") (pintype "input"))
      (node (ref "R7") (pin "2") (pinfunction "2_2") (pintype "passive"))
      (node (ref "RP4") (pin "8") (pinfunction "8_8") (pintype "passive"))
    )
    (net (code "42") (name "Net-(EB2A-O)") (class "Default")
      (node (ref "EB2") (pin "12") (pinfunction "O_12") (pintype "output"))
      (node (ref "EB3") (pin "5") (pinfunction "D2_5") (pintype "input"))
    )
    (net (code "43") (name "Net-(EB2B-I)") (class "Default")
      (node (ref "C9") (pin "1") (pinfunction "1_1") (pintype "passive"))
      (node (ref "EB2") (pin "11") (pinfunction "I_11") (pintype "input"))
      (node (ref "R9") (pin "2") (pinfunction "2_2") (pintype "passive"))
      (node (ref "RP3") (pin "2") (pinfunction "2_2") (pintype "passive"))
    )
    (net (code "44") (name "Net-(EB2D-I)") (class "Default")
      (node (ref "C6") (pin "1") (pinfunction "1_1") (pintype "passive"))
      (node (ref "EB2") (pin "1") (pinfunction "I_1") (pintype "input"))
      (node (ref "R6") (pin "2") (pinfunction "2_2") (pintype "passive"))
      (node (ref "RP3") (pin "4") (pinfunction "4_4") (pintype "passive"))
    )
    (net (code "45") (name "Net-(EB2D-O)") (class "Default")
      (node (ref "EB2") (pin "2") (pinfunction "O_2") (pintype "output"))
      (node (ref "EB3") (pin "13") (pinfunction "D4_13") (pintype "input"))
    )
    (net (code "46") (name "Net-(EB2E-I)") (class "Default")
      (node (ref "C8") (pin "1") (pinfunction "1_1") (pintype "passive"))
      (node (ref "EB2") (pin "3") (pinfunction "I_3") (pintype "input"))
      (node (ref "R8") (pin "2") (pinfunction "2_2") (pintype "passive"))
      (node (ref "RP3") (pin "3") (pinfunction "3_3") (pintype "passive"))
    )
    (net (code "47") (name "Net-(EB2E-O)") (class "Default")
      (node (ref "EB2") (pin "4") (pinfunction "O_4") (pintype "output"))
      (node (ref "EB3") (pin "12") (pinfunction "D3_12") (pintype "input"))
    )
    (net (code "48") (name "Net-(EB2F-I)") (class "Default")
      (node (ref "EB2") (pin "5") (pinfunction "I_5") (pintype "input"))
      (node (ref "EC4") (pin "2") (pinfunction "O_2") (pintype "output"))
    )
    (net (code "49") (name "Net-(EB2F-O)") (class "Default")
      (node (ref "EB2") (pin "6") (pinfunction "O_6") (pintype "output"))
      (node (ref "EC4") (pin "11") (pinfunction "I0_11") (pintype "input"))
      (node (ref "EC4") (pin "9") (pinfunction "I0_9") (pintype "input"))
      (node (ref "ED2") (pin "10") (pinfunction "I1_10") (pintype "input"))
      (node (ref "ED2") (pin "4") (pinfunction "I0_4") (pintype "input"))
      (node (ref "ED2") (pin "6") (pinfunction "I0_6") (pintype "input"))
      (node (ref "ED3") (pin "10") (pinfunction "I1_10") (pintype "input"))
      (node (ref "ED3") (pin "12") (pinfunction "I1_12") (pintype "input"))
      (node (ref "ED3") (pin "4") (pinfunction "I0_4") (pintype "input"))
      (node (ref "ED3") (pin "6") (pinfunction "I0_6") (pintype "input"))
      (node (ref "ED4") (pin "9") (pinfunction "I3_9") (pintype "input"))
      (node (ref "R15") (pin "2") (pinfunction "2_2") (pintype "passive"))
    )
    (net (code "50") (name "Net-(EB3A-~{Q1})") (class "Default")
      (node (ref "EB3") (pin "3") (pinfunction "~{Q1}_3") (pintype "output"))
      (node (ref "EB4") (pin "3") (pinfunction "I1_3") (pintype "input"))
    )
    (net (code "51") (name "Net-(EB3A-~{Q2})") (class "Default")
      (node (ref "EB3") (pin "6") (pinfunction "~{Q2}_6") (pintype "output"))
      (node (ref "EB4") (pin "8") (pinfunction "I0_8") (pintype "input"))
    )
    (net (code "52") (name "Net-(EB3A-~{Q3})") (class "Default")
      (node (ref "EB3") (pin "11") (pinfunction "~{Q3}_11") (pintype "output"))
      (node (ref "EB4") (pin "5") (pinfunction "I0_5") (pintype "input"))
    )
    (net (code "53") (name "Net-(EB3A-~{Q4})") (class "Default")
      (node (ref "EB3") (pin "14") (pinfunction "~{Q4}_14") (pintype "output"))
      (node (ref "EB4") (pin "11") (pinfunction "I0_11") (pintype "input"))
    )
    (net (code "54") (name "Net-(EB5A-I0)") (class "Default")
      (node (ref "EB5") (pin "1") (pinfunction "I0_1") (pintype "input"))
      (node (ref "EC7") (pin "6") (pinfunction "O_6") (pintype "output"))
    )
    (net (code "55") (name "Net-(EB5A-O)") (class "Default")
      (node (ref "EB5") (pin "3") (pinfunction "O_3") (pintype "output"))
      (node (ref "ED7") (pin "1") (pinfunction "I_1") (pintype "input"))
    )
    (net (code "56") (name "Net-(EB5C-I0)") (class "Default")
      (node (ref "EB5") (pin "9") (pinfunction "I0_9") (pintype "input"))
      (node (ref "EB6") (pin "9") (pinfunction "Q_9") (pintype "output"))
    )
    (net (code "57") (name "Net-(EB5C-O)") (class "Default")
      (node (ref "EB5") (pin "8") (pinfunction "O_8") (pintype "output"))
      (node (ref "EB6") (pin "11") (pinfunction "CLK_11") (pintype "input"))
    )
    (net (code "58") (name "Net-(EB5D-I0)") (class "Default")
      (node (ref "EB5") (pin "12") (pinfunction "I0_12") (pintype "input"))
      (node (ref "EB6") (pin "6") (pinfunction "~{Q}_6") (pintype "output"))
    )
    (net (code "59") (name "Net-(EB5D-O)") (class "Default")
      (node (ref "EB5") (pin "11") (pinfunction "O_11") (pintype "output"))
      (node (ref "EB6") (pin "3") (pinfunction "CLK_3") (pintype "input"))
    )
    (net (code "60") (name "Net-(EB6B-~{Q})") (class "Default")
      (node (ref "EB6") (pin "8") (pinfunction "~{Q}_8") (pintype "output"))
      (node (ref "ED6") (pin "9") (pinfunction "I0_9") (pintype "input"))
    )
    (net (code "61") (name "Net-(EB7B-CLK)") (class "Default")
      (node (ref "EB7") (pin "11") (pinfunction "CLK_11") (pintype "input"))
      (node (ref "ED6") (pin "8") (pinfunction "O_8") (pintype "output"))
    )
    (net (code "62") (name "Net-(EB7B-CLR)") (class "Default")
      (node (ref "EB7") (pin "13") (pinfunction "CLR_13") (pintype "input"))
      (node (ref "ED7") (pin "2") (pinfunction "O_2") (pintype "output"))
    )
    (net (code "63") (name "Net-(EB7B-Q)") (class "Default")
      (node (ref "EB7") (pin "9") (pinfunction "Q_9") (pintype "output"))
      (node (ref "EC6") (pin "5") (pinfunction "I0_5") (pintype "input"))
      (node (ref "EC6") (pin "9") (pinfunction "I1_9") (pintype "input"))
    )
    (net (code "64") (name "Net-(EC1D-O)") (class "Default")
      (node (ref "EC1") (pin "11") (pinfunction "O_11") (pintype "output"))
      (node (ref "ED5") (pin "4") (pinfunction "I0_4") (pintype "input"))
    )
    (net (code "65") (name "Net-(EC2A-A)") (class "Default")
      (node (ref "EC2") (pin "1") (pinfunction "A_1") (pintype "input"))
      (node (ref "EC3") (pin "1") (pinfunction "A_1") (pintype "input"))
      (node (ref "ED2") (pin "14") (pinfunction "O_14") (pintype "output"))
    )
    (net (code "66") (name "Net-(EC2A-B)") (class "Default")
      (node (ref "EC2") (pin "2") (pinfunction "B_2") (pintype "input"))
      (node (ref "EC3") (pin "2") (pinfunction "B_2") (pintype "input"))
      (node (ref "ED2") (pin "3") (pinfunction "O_3") (pintype "output"))
    )
    (net (code "67") (name "Net-(EC2A-C)") (class "Default")
      (node (ref "EC2") (pin "3") (pinfunction "C_3") (pintype "input"))
      (node (ref "EC3") (pin "3") (pinfunction "C_3") (pintype "input"))
      (node (ref "ED2") (pin "2") (pinfunction "O_2") (pintype "output"))
    )
    (net (code "68") (name "Net-(EC2A-G2A)") (class "Default")
      (node (ref "EC2") (pin "4") (pinfunction "G2A_4") (pintype "input"))
      (node (ref "ED5") (pin "11") (pinfunction "O_11") (pintype "output"))
    )
    (net (code "69") (name "Net-(EC2A-G2B)") (class "Default")
      (node (ref "EC2") (pin "5") (pinfunction "G2B_5") (pintype "input"))
      (node (ref "ED7") (pin "4") (pinfunction "O_4") (pintype "output"))
    )
    (net (code "70") (name "Net-(EC3A-G2A)") (class "Default")
      (node (ref "EC3") (pin "4") (pinfunction "G2A_4") (pintype "input"))
      (node (ref "ED7") (pin "6") (pinfunction "O_6") (pintype "output"))
    )
    (net (code "71") (name "Net-(EC3A-G2B)") (class "Default")
      (node (ref "EC3") (pin "5") (pinfunction "G2B_5") (pintype "input"))
      (node (ref "EC4") (pin "14") (pinfunction "O_14") (pintype "output"))
      (node (ref "ED7") (pin "3") (pinfunction "I_3") (pintype "input"))
    )
    (net (code "72") (name "Net-(EC4D-O)") (class "Default")
      (node (ref "EC4") (pin "13") (pinfunction "O_13") (pintype "output"))
      (node (ref "ED5") (pin "13") (pinfunction "I1_13") (pintype "input"))
      (node (ref "ED7") (pin "5") (pinfunction "I_5") (pintype "input"))
    )
    (net (code "73") (name "Net-(EC5A-CLR)") (class "Default")
      (node (ref "EC5") (pin "1") (pinfunction "CLR_1") (pintype "input"))
      (node (ref "ED6") (pin "11") (pinfunction "O_11") (pintype "output"))
    )
    (net (code "74") (name "Net-(EC5B-PRE)") (class "Default")
      (node (ref "EC5") (pin "10") (pinfunction "PRE_10") (pintype "input"))
      (node (ref "ED6") (pin "3") (pinfunction "O_3") (pintype "output"))
    )
    (net (code "75") (name "Net-(EC5B-Q)") (class "Default")
      (node (ref "EC5") (pin "9") (pinfunction "Q_9") (pintype "output"))
      (node (ref "EC6") (pin "8") (pinfunction "I0_8") (pintype "input"))
    )
    (net (code "76") (name "Net-(EC6A-I0)") (class "Default")
      (node (ref "EC6") (pin "2") (pinfunction "I0_2") (pintype "input"))
      (node (ref "R16") (pin "2") (pinfunction "2_2") (pintype "passive"))
    )
    (net (code "77") (name "Net-(EC7B-I0)") (class "Default")
      (node (ref "EC7") (pin "4") (pinfunction "I0_4") (pintype "input"))
      (node (ref "ED6") (pin "6") (pinfunction "O_6") (pintype "output"))
    )
    (net (code "78") (name "Net-(ED3A-O)") (class "Default")
      (node (ref "ED3") (pin "3") (pinfunction "O_3") (pintype "output"))
      (node (ref "ED4") (pin "10") (pinfunction "I4_10") (pintype "input"))
      (node (ref "ED4") (pin "11") (pinfunction "I5_11") (pintype "input"))
      (node (ref "ED4") (pin "12") (pinfunction "I6_12") (pintype "input"))
    )
    (net (code "79") (name "Net-(ED3B-O)") (class "Default")
      (node (ref "ED3") (pin "2") (pinfunction "O_2") (pintype "output"))
      (node (ref "ED4") (pin "6") (pinfunction "I2_6") (pintype "input"))
    )
    (net (code "80") (name "Net-(ED3C-O)") (class "Default")
      (node (ref "ED3") (pin "14") (pinfunction "O_14") (pintype "output"))
      (node (ref "ED4") (pin "4") (pinfunction "I0_4") (pintype "input"))
    )
    (net (code "81") (name "Net-(ED3D-O)") (class "Default")
      (node (ref "ED3") (pin "13") (pinfunction "O_13") (pintype "output"))
      (node (ref "ED4") (pin "5") (pinfunction "I1_5") (pintype "input"))
    )
    (net (code "82") (name "Net-(ED5A-I1)") (class "Default")
      (node (ref "ED5") (pin "2") (pinfunction "I1_2") (pintype "input"))
      (node (ref "ED5") (pin "6") (pinfunction "O_6") (pintype "output"))
    )
    (net (code "83") (name "Net-(ED7E-O)") (class "Default")
      (node (ref "ED7") (pin "10") (pinfunction "O_10") (pintype "output"))
      (node (ref "ED7") (pin "13") (pinfunction "I_13") (pintype "input"))
    )
    (net (code "84") (name "Net-(P1-PadE)") (class "Default")
      (node (ref "P1") (pin "E") (pinfunction "E_E") (pintype "passive"))
      (node (ref "P1") (pin "S") (pinfunction "S_S") (pintype "passive"))
      (node (ref "R14") (pin "1") (pinfunction "1_1") (pintype "passive"))
    )
    (net (code "85") (name "Net-(P2-PadE)") (class "Default")
      (node (ref "P2") (pin "E") (pinfunction "E_E") (pintype "passive"))
      (node (ref "P2") (pin "S") (pinfunction "S_S") (pintype "passive"))
      (node (ref "R12") (pin "1") (pinfunction "1_1") (pintype "passive"))
    )
    (net (code "86") (name "Net-(P3-PadE)") (class "Default")
      (node (ref "P3") (pin "E") (pinfunction "E_E") (pintype "passive"))
      (node (ref "P3") (pin "S") (pinfunction "S_S") (pintype "passive"))
      (node (ref "R11") (pin "1") (pinfunction "1_1") (pintype "passive"))
    )
    (net (code "87") (name "PTERR") (class "Default")
      (node (ref "J1") (pin "R") (pinfunction "P$2_R") (pintype "passive"))
      (node (ref "R10") (pin "1") (pinfunction "1_1") (pintype "passive"))
      (node (ref "RP2") (pin "8") (pinfunction "8_8") (pintype "passive"))
    )
    (net (code "88") (name "PTR04") (class "Default")
      (node (ref "J1") (pin "N") (pinfunction "P$2_N") (pintype "passive"))
      (node (ref "R1") (pin "1") (pinfunction "1_1") (pintype "passive"))
      (node (ref "RP1") (pin "2") (pinfunction "2_2") (pintype "passive"))
    )
    (net (code "89") (name "PTR05") (class "Default")
      (node (ref "J1") (pin "J") (pinfunction "P$2_J") (pintype "passive"))
      (node (ref "R3") (pin "1") (pinfunction "1_1") (pintype "passive"))
      (node (ref "RP1") (pin "5") (pinfunction "5_5") (pintype "passive"))
    )
    (net (code "90") (name "PTR06") (class "Default")
      (node (ref "J1") (pin "F") (pinfunction "P$2_F") (pintype "passive"))
      (node (ref "R4") (pin "1") (pinfunction "1_1") (pintype "passive"))
      (node (ref "RP1") (pin "6") (pinfunction "6_6") (pintype "passive"))
    )
    (net (code "91") (name "PTR07") (class "Default")
      (node (ref "J1") (pin "L") (pinfunction "P$2_L") (pintype "passive"))
      (node (ref "R2") (pin "1") (pinfunction "1_1") (pintype "passive"))
      (node (ref "RP1") (pin "3") (pinfunction "3_3") (pintype "passive"))
    )
    (net (code "92") (name "PTR08") (class "Default")
      (node (ref "J1") (pin "D") (pinfunction "P$2_D") (pintype "passive"))
      (node (ref "R5") (pin "1") (pinfunction "1_1") (pintype "passive"))
      (node (ref "RP1") (pin "8") (pinfunction "8_8") (pintype "passive"))
    )
    (net (code "93") (name "PTR09") (class "Default")
      (node (ref "J1") (pin "T") (pinfunction "P$2_T") (pintype "passive"))
      (node (ref "R7") (pin "1") (pinfunction "1_1") (pintype "passive"))
      (node (ref "RP2") (pin "4") (pinfunction "4_4") (pintype "passive"))
    )
    (net (code "94") (name "PTR10") (class "Default")
      (node (ref "J1") (pin "V") (pinfunction "P$2_V") (pintype "passive"))
      (node (ref "R8") (pin "1") (pinfunction "1_1") (pintype "passive"))
      (node (ref "RP2") (pin "5") (pinfunction "5_5") (pintype "passive"))
    )
    (net (code "95") (name "PTR11") (class "Default")
      (node (ref "J1") (pin "B") (pinfunction "P$2_B") (pintype "passive"))
      (node (ref "R6") (pin "1") (pinfunction "1_1") (pintype "passive"))
      (node (ref "RP2") (pin "2") (pinfunction "2_2") (pintype "passive"))
    )
    (net (code "96") (name "PTSTROBE") (class "Default")
      (node (ref "J1") (pin "X") (pinfunction "P$2_X") (pintype "passive"))
      (node (ref "R9") (pin "1") (pinfunction "1_1") (pintype "passive"))
      (node (ref "RP2") (pin "7") (pinfunction "7_7") (pintype "passive"))
    )
    (net (code "97") (name "RUN") (class "Default")
      (node (ref "EA5") (pin "9") (pinfunction "A_9") (pintype "input"))
      (node (ref "EA6") (pin "5") (pinfunction "Q_5") (pintype "output"))
      (node (ref "EA7") (pin "1") (pinfunction "A1_1") (pintype "input"))
    )
    (net (code "98") (name "STOP") (class "Default")
      (node (ref "EA6") (pin "12") (pinfunction "~{Q}_12") (pintype "output"))
      (node (ref "EA6") (pin "3") (pinfunction "R_3") (pintype "input"))
      (node (ref "EB6") (pin "1") (pinfunction "CLR_1") (pintype "input"))
      (node (ref "EB6") (pin "10") (pinfunction "PRE_10") (pintype "input"))
    )
    (net (code "99") (name "STOPPED") (class "Default")
      (node (ref "EA5") (pin "12") (pinfunction "~{Q}_12") (pintype "output"))
      (node (ref "ED6") (pin "10") (pinfunction "I1_10") (pintype "input"))
      (node (ref "ED6") (pin "12") (pinfunction "I0_12") (pintype "input"))
    )
    (net (code "100") (name "TP3") (class "Default")
      (node (ref "EC4") (pin "4") (pinfunction "I0_4") (pintype "input"))
      (node (ref "EC4") (pin "5") (pinfunction "I1_5") (pintype "input"))
      (node (ref "U$2") (pin "CH2") (pinfunction "1_CH2") (pintype "bidirectional"))
    )
    (net (code "101") (name "VCC") (class "Default")
      (node (ref "C15") (pin "+") (pinfunction "+_+") (pintype "passive"))
      (node (ref "C16") (pin "+") (pinfunction "+_+") (pintype "passive"))
      (node (ref "C17") (pin "+") (pinfunction "+_+") (pintype "passive"))
      (node (ref "C18") (pin "+") (pinfunction "+_+") (pintype "passive"))
      (node (ref "C19") (pin "+") (pinfunction "+_+") (pintype "passive"))
      (node (ref "C20") (pin "+") (pinfunction "+_+") (pintype "passive"))
      (node (ref "C21") (pin "+") (pinfunction "+_+") (pintype "passive"))
      (node (ref "C22") (pin "+") (pinfunction "+_+") (pintype "passive"))
      (node (ref "C23") (pin "+") (pinfunction "+_+") (pintype "passive"))
      (node (ref "C24") (pin "+") (pinfunction "+_+") (pintype "passive"))
      (node (ref "C25") (pin "+") (pinfunction "+_+") (pintype "passive"))
      (node (ref "C26") (pin "+") (pinfunction "+_+") (pintype "passive"))
      (node (ref "C29") (pin "1") (pinfunction "1_1") (pintype "passive"))
      (node (ref "C30") (pin "1") (pinfunction "1_1") (pintype "passive"))
      (node (ref "C31") (pin "1") (pinfunction "1_1") (pintype "passive"))
      (node (ref "C32") (pin "1") (pinfunction "1_1") (pintype "passive"))
      (node (ref "C33") (pin "1") (pinfunction "1_1") (pintype "passive"))
      (node (ref "C34") (pin "1") (pinfunction "1_1") (pintype "passive"))
      (node (ref "C35") (pin "1") (pinfunction "1_1") (pintype "passive"))
      (node (ref "C36") (pin "1") (pinfunction "1_1") (pintype "passive"))
      (node (ref "C37") (pin "1") (pinfunction "1_1") (pintype "passive"))
      (node (ref "C38") (pin "1") (pinfunction "1_1") (pintype "passive"))
      (node (ref "C39") (pin "1") (pinfunction "1_1") (pintype "passive"))
      (node (ref "C40") (pin "1") (pinfunction "1_1") (pintype "passive"))
      (node (ref "C41") (pin "1") (pinfunction "1_1") (pintype "passive"))
      (node (ref "C42") (pin "1") (pinfunction "1_1") (pintype "passive"))
      (node (ref "C43") (pin "1") (pinfunction "1_1") (pintype "passive"))
      (node (ref "C44") (pin "1") (pinfunction "1_1") (pintype "passive"))
      (node (ref "C45") (pin "1") (pinfunction "1_1") (pintype "passive"))
      (node (ref "C46") (pin "1") (pinfunction "1_1") (pintype "passive"))
      (node (ref "C47") (pin "1") (pinfunction "1_1") (pintype "passive"))
      (node (ref "C48") (pin "1") (pinfunction "1_1") (pintype "passive"))
      (node (ref "C49") (pin "1") (pinfunction "1_1") (pintype "passive"))
      (node (ref "C50") (pin "1") (pinfunction "1_1") (pintype "passive"))
      (node (ref "C51") (pin "1") (pinfunction "1_1") (pintype "passive"))
      (node (ref "C52") (pin "1") (pinfunction "1_1") (pintype "passive"))
      (node (ref "C53") (pin "1") (pinfunction "1_1") (pintype "passive"))
      (node (ref "EA2") (pin "9") (pinfunction "I_9") (pintype "input"))
      (node (ref "EA3") (pin "1") (pinfunction "CLR_1") (pintype "input"))
      (node (ref "EA5") (pin "10") (pinfunction "B_10") (pintype "input"))
      (node (ref "EA5") (pin "11") (pinfunction "R_11") (pintype "input"))
      (node (ref "EA5") (pin "2") (pinfunction "B_2") (pintype "input"))
      (node (ref "EA6") (pin "11") (pinfunction "R_11") (pintype "input"))
      (node (ref "EA7") (pin "15") (pinfunction "A4_15") (pintype "input"))
      (node (ref "EA7") (pin "4") (pinfunction "G_4") (pintype "input"))
      (node (ref "EA7") (pin "9") (pinfunction "A3_9") (pintype "input"))
      (node (ref "EB3") (pin "1") (pinfunction "CLR_1") (pintype "input"))
      (node (ref "EB6") (pin "4") (pinfunction "PRE_4") (pintype "input"))
      (node (ref "EB7") (pin "10") (pinfunction "PRE_10") (pintype "input"))
      (node (ref "EB7") (pin "12") (pinfunction "D_12") (pintype "input"))
      (node (ref "EC1") (pin "1") (pinfunction "I0_1") (pintype "input"))
      (node (ref "EC1") (pin "10") (pinfunction "I1_10") (pintype "input"))
      (node (ref "EC1") (pin "2") (pinfunction "I1_2") (pintype "input"))
      (node (ref "EC1") (pin "4") (pinfunction "I0_4") (pintype "input"))
      (node (ref "EC1") (pin "5") (pinfunction "I1_5") (pintype "input"))
      (node (ref "EC1") (pin "9") (pinfunction "I0_9") (pintype "input"))
      (node (ref "EC5") (pin "11") (pinfunction "CLK_11") (pintype "input"))
      (node (ref "EC5") (pin "12") (pinfunction "D_12") (pintype "input"))
      (node (ref "EC5") (pin "2") (pinfunction "D_2") (pintype "input"))
      (node (ref "EC5") (pin "4") (pinfunction "PRE_4") (pintype "input"))
      (node (ref "EC7") (pin "12") (pinfunction "I0_12") (pintype "input"))
      (node (ref "EC7") (pin "13") (pinfunction "I1_13") (pintype "input"))
      (node (ref "P1") (pin "A") (pinfunction "A_A") (pintype "passive"))
      (node (ref "P2") (pin "A") (pinfunction "A_A") (pintype "passive"))
      (node (ref "P3") (pin "A") (pinfunction "A_A") (pintype "passive"))
      (node (ref "R13") (pin "1") (pinfunction "1_1") (pintype "passive"))
      (node (ref "R15") (pin "1") (pinfunction "1_1") (pintype "passive"))
      (node (ref "R16") (pin "1") (pinfunction "1_1") (pintype "passive"))
      (node (ref "R17") (pin "2") (pinfunction "2_2") (pintype "passive"))
      (node (ref "R19") (pin "2") (pinfunction "2_2") (pintype "passive"))
      (node (ref "R21") (pin "2") (pinfunction "2_2") (pintype "passive"))
      (node (ref "R23") (pin "2") (pinfunction "2_2") (pintype "passive"))
      (node (ref "RP1") (pin "1") (pinfunction "1_1") (pintype "passive"))
      (node (ref "RP2") (pin "1") (pinfunction "1_1") (pintype "passive"))
      (node (ref "U$2") (pin "AA2") (pinfunction "1_AA2") (pintype "bidirectional"))
      (node (ref "U$2") (pin "BA2") (pinfunction "1_BA2") (pintype "bidirectional"))
      (node (ref "U$2") (pin "CA2") (pinfunction "1_CA2") (pintype "bidirectional"))
    )
    (net (code "102") (name "unconnected-(EA2C-O-Pad8)") (class "Default")
      (node (ref "EA2") (pin "8") (pinfunction "O_8") (pintype "output"))
    )
    (net (code "103") (name "unconnected-(EA3A-Q1-Pad2)") (class "Default")
      (node (ref "EA3") (pin "2") (pinfunction "Q1_2") (pintype "output"))
    )
    (net (code "104") (name "unconnected-(EA3A-Q2-Pad7)") (class "Default")
      (node (ref "EA3") (pin "7") (pinfunction "Q2_7") (pintype "output"))
    )
    (net (code "105") (name "unconnected-(EA3A-Q3-Pad10)") (class "Default")
      (node (ref "EA3") (pin "10") (pinfunction "Q3_10") (pintype "output"))
    )
    (net (code "106") (name "unconnected-(EA3A-Q4-Pad15)") (class "Default")
      (node (ref "EA3") (pin "15") (pinfunction "Q4_15") (pintype "output"))
    )
    (net (code "107") (name "unconnected-(EA5A-~{Q}-Pad4)") (class "Default")
      (node (ref "EA5") (pin "4") (pinfunction "~{Q}_4") (pintype "output"))
    )
    (net (code "108") (name "unconnected-(EA5B-Q-Pad5)") (class "Default")
      (node (ref "EA5") (pin "5") (pinfunction "Q_5") (pintype "output"))
    )
    (net (code "109") (name "unconnected-(EA6A-~{Q}-Pad4)") (class "Default")
      (node (ref "EA6") (pin "4") (pinfunction "~{Q}_4") (pintype "output"))
    )
    (net (code "110") (name "unconnected-(EA7A-Y3-Pad10)") (class "Default")
      (node (ref "EA7") (pin "10") (pinfunction "Y3_10") (pintype "output"))
    )
    (net (code "111") (name "unconnected-(EA7A-Y4-Pad14)") (class "Default")
      (node (ref "EA7") (pin "14") (pinfunction "Y4_14") (pintype "output"))
    )
    (net (code "112") (name "unconnected-(EA7A-Z3-Pad11)") (class "Default")
      (node (ref "EA7") (pin "11") (pinfunction "Z3_11") (pintype "output"))
    )
    (net (code "113") (name "unconnected-(EA7A-Z4-Pad13)") (class "Default")
      (node (ref "EA7") (pin "13") (pinfunction "Z4_13") (pintype "output"))
    )
    (net (code "114") (name "unconnected-(EB3A-Q1-Pad2)") (class "Default")
      (node (ref "EB3") (pin "2") (pinfunction "Q1_2") (pintype "output"))
    )
    (net (code "115") (name "unconnected-(EB3A-Q2-Pad7)") (class "Default")
      (node (ref "EB3") (pin "7") (pinfunction "Q2_7") (pintype "output"))
    )
    (net (code "116") (name "unconnected-(EB3A-Q3-Pad10)") (class "Default")
      (node (ref "EB3") (pin "10") (pinfunction "Q3_10") (pintype "output"))
    )
    (net (code "117") (name "unconnected-(EB3A-Q4-Pad15)") (class "Default")
      (node (ref "EB3") (pin "15") (pinfunction "Q4_15") (pintype "output"))
    )
    (net (code "118") (name "unconnected-(EB7A-Q-Pad5)") (class "Default")
      (node (ref "EB7") (pin "5") (pinfunction "Q_5") (pintype "output"))
    )
    (net (code "119") (name "unconnected-(EB7B-~{Q}-Pad8)") (class "Default")
      (node (ref "EB7") (pin "8") (pinfunction "~{Q}_8") (pintype "output"))
    )
    (net (code "120") (name "unconnected-(EC1A-O-Pad3)") (class "Default")
      (node (ref "EC1") (pin "3") (pinfunction "O_3") (pintype "output"))
    )
    (net (code "121") (name "unconnected-(EC1B-O-Pad6)") (class "Default")
      (node (ref "EC1") (pin "6") (pinfunction "O_6") (pintype "output"))
    )
    (net (code "122") (name "unconnected-(EC1C-O-Pad8)") (class "Default")
      (node (ref "EC1") (pin "8") (pinfunction "O_8") (pintype "output"))
    )
    (net (code "123") (name "unconnected-(EC2A-Y1-Pad14)") (class "Default")
      (node (ref "EC2") (pin "14") (pinfunction "Y1_14") (pintype "output"))
    )
    (net (code "124") (name "unconnected-(EC2A-Y2-Pad13)") (class "Default")
      (node (ref "EC2") (pin "13") (pinfunction "Y2_13") (pintype "output"))
    )
    (net (code "125") (name "unconnected-(EC2A-Y3-Pad12)") (class "Default")
      (node (ref "EC2") (pin "12") (pinfunction "Y3_12") (pintype "output"))
    )
    (net (code "126") (name "unconnected-(EC2A-Y4-Pad11)") (class "Default")
      (node (ref "EC2") (pin "11") (pinfunction "Y4_11") (pintype "output"))
    )
    (net (code "127") (name "unconnected-(EC2A-Y5-Pad10)") (class "Default")
      (node (ref "EC2") (pin "10") (pinfunction "Y5_10") (pintype "output"))
    )
    (net (code "128") (name "unconnected-(EC2A-Y6-Pad9)") (class "Default")
      (node (ref "EC2") (pin "9") (pinfunction "Y6_9") (pintype "output"))
    )
    (net (code "129") (name "unconnected-(EC2A-Y7-Pad7)") (class "Default")
      (node (ref "EC2") (pin "7") (pinfunction "Y7_7") (pintype "output"))
    )
    (net (code "130") (name "unconnected-(EC3A-Y7-Pad7)") (class "Default")
      (node (ref "EC3") (pin "7") (pinfunction "Y7_7") (pintype "output"))
    )
    (net (code "131") (name "unconnected-(EC5B-~{Q}-Pad8)") (class "Default")
      (node (ref "EC5") (pin "8") (pinfunction "~{Q}_8") (pintype "output"))
    )
    (net (code "132") (name "unconnected-(EC7D-O-Pad11)") (class "Default")
      (node (ref "EC7") (pin "11") (pinfunction "O_11") (pintype "output"))
    )
    (net (code "133") (name "unconnected-(RP1-Pad4)") (class "Default")
      (node (ref "RP1") (pin "4") (pinfunction "4_4") (pintype "passive"))
    )
    (net (code "134") (name "unconnected-(RP1-Pad7)") (class "Default")
      (node (ref "RP1") (pin "7") (pinfunction "7_7") (pintype "passive"))
    )
    (net (code "135") (name "unconnected-(RP2-Pad3)") (class "Default")
      (node (ref "RP2") (pin "3") (pinfunction "3_3") (pintype "passive"))
    )
    (net (code "136") (name "unconnected-(RP2-Pad6)") (class "Default")
      (node (ref "RP2") (pin "6") (pinfunction "6_6") (pintype "passive"))
    )
    (net (code "137") (name "unconnected-(RP4-Pad2)") (class "Default")
      (node (ref "RP4") (pin "2") (pinfunction "2_2") (pintype "passive"))
    )
    (net (code "138") (name "unconnected-(RP4-Pad3)") (class "Default")
      (node (ref "RP4") (pin "3") (pinfunction "3_3") (pintype "passive"))
    )
    (net (code "139") (name "unconnected-(RP4-Pad4)") (class "Default")
      (node (ref "RP4") (pin "4") (pinfunction "4_4") (pintype "passive"))
    )
    (net (code "140") (name "unconnected-(RP4-Pad5)") (class "Default")
      (node (ref "RP4") (pin "5") (pinfunction "5_5") (pintype "passive"))
    )
    (net (code "141") (name "~{C1}") (class "Default")
      (node (ref "EC6") (pin "1") (pinfunction "O_1") (pintype "open_collector"))
      (node (ref "U$2") (pin "CH1") (pinfunction "1_CH1") (pintype "bidirectional"))
    )
    (net (code "142") (name "~{DATA4}") (class "Default")
      (node (ref "EA4") (pin "1") (pinfunction "O_1") (pintype "open_collector"))
      (node (ref "U$2") (pin "BR1") (pinfunction "1_BR1") (pintype "bidirectional"))
    )
    (net (code "143") (name "~{DATA5}") (class "Default")
      (node (ref "EA4") (pin "10") (pinfunction "O_10") (pintype "open_collector"))
      (node (ref "U$2") (pin "BS1") (pinfunction "1_BS1") (pintype "bidirectional"))
    )
    (net (code "144") (name "~{DATA6}") (class "Default")
      (node (ref "EA4") (pin "4") (pinfunction "O_4") (pintype "open_collector"))
      (node (ref "U$2") (pin "BU1") (pinfunction "1_BU1") (pintype "bidirectional"))
    )
    (net (code "145") (name "~{DATA7}") (class "Default")
      (node (ref "EA4") (pin "13") (pinfunction "O_13") (pintype "open_collector"))
      (node (ref "U$2") (pin "BV1") (pinfunction "1_BV1") (pintype "bidirectional"))
    )
    (net (code "146") (name "~{DATA8}") (class "Default")
      (node (ref "EB4") (pin "1") (pinfunction "O_1") (pintype "open_collector"))
      (node (ref "U$2") (pin "DR1") (pinfunction "1_DR1") (pintype "bidirectional"))
    )
    (net (code "147") (name "~{DATA9}") (class "Default")
      (node (ref "EB4") (pin "10") (pinfunction "O_10") (pintype "open_collector"))
      (node (ref "U$2") (pin "DS1") (pinfunction "1_DS1") (pintype "bidirectional"))
    )
    (net (code "148") (name "~{DATA10}") (class "Default")
      (node (ref "EB4") (pin "4") (pinfunction "O_4") (pintype "open_collector"))
      (node (ref "U$2") (pin "DU1") (pinfunction "1_DU1") (pintype "bidirectional"))
    )
    (net (code "149") (name "~{DATA11}") (class "Default")
      (node (ref "EB4") (pin "13") (pinfunction "O_13") (pintype "open_collector"))
      (node (ref "U$2") (pin "DV1") (pinfunction "1_DV1") (pintype "bidirectional"))
    )
    (net (code "150") (name "~{FETCH}") (class "Default")
      (node (ref "EC5") (pin "3") (pinfunction "CLK_3") (pintype "input"))
      (node (ref "ED5") (pin "3") (pinfunction "O_3") (pintype "output"))
      (node (ref "ED6") (pin "5") (pinfunction "I1_5") (pintype "input"))
    )
    (net (code "151") (name "~{INITIALIZE}") (class "Default")
      (node (ref "EB5") (pin "2") (pinfunction "I1_2") (pintype "input"))
      (node (ref "EB6") (pin "13") (pinfunction "CLR_13") (pintype "input"))
      (node (ref "EB7") (pin "3") (pinfunction "CLK_3") (pintype "input"))
      (node (ref "ED2") (pin "13") (pinfunction "O_13") (pintype "output"))
      (node (ref "ED6") (pin "13") (pinfunction "I1_13") (pintype "input"))
      (node (ref "ED6") (pin "2") (pinfunction "I1_2") (pintype "input"))
    )
    (net (code "152") (name "~{INTERNAL_IO}") (class "Default")
      (node (ref "EC6") (pin "13") (pinfunction "O_13") (pintype "open_collector"))
      (node (ref "U$2") (pin "CL1") (pinfunction "1_CL1") (pintype "bidirectional"))
    )
    (net (code "153") (name "~{INT_RQST}") (class "Default")
      (node (ref "EC6") (pin "10") (pinfunction "O_10") (pintype "open_collector"))
      (node (ref "U$2") (pin "CP1") (pinfunction "1_CP1") (pintype "bidirectional"))
    )
    (net (code "154") (name "~{IOT010}") (class "Default")
      (node (ref "EC3") (pin "15") (pinfunction "Y0_15") (pintype "output"))
      (node (ref "ED5") (pin "10") (pinfunction "I1_10") (pintype "input"))
    )
    (net (code "155") (name "~{IOT011}") (class "Default")
      (node (ref "EB2") (pin "9") (pinfunction "I_9") (pintype "input"))
      (node (ref "EC3") (pin "14") (pinfunction "Y1_14") (pintype "output"))
    )
    (net (code "156") (name "~{IOT012}") (class "Default")
      (node (ref "EB5") (pin "4") (pinfunction "I0_4") (pintype "input"))
      (node (ref "EC3") (pin "13") (pinfunction "Y2_13") (pintype "output"))
      (node (ref "ED6") (pin "4") (pinfunction "I0_4") (pintype "input"))
    )
    (net (code "157") (name "~{IOT013}") (class "Default")
      (node (ref "EC3") (pin "12") (pinfunction "Y3_12") (pintype "output"))
      (node (ref "EC7") (pin "9") (pinfunction "I0_9") (pintype "input"))
    )
    (net (code "158") (name "~{IOT014}") (class "Default")
      (node (ref "EC1") (pin "13") (pinfunction "I1_13") (pintype "input"))
      (node (ref "EC3") (pin "11") (pinfunction "Y4_11") (pintype "output"))
    )
    (net (code "159") (name "~{IOT015}") (class "Default")
      (node (ref "EC3") (pin "10") (pinfunction "Y5_10") (pintype "output"))
      (node (ref "EC7") (pin "1") (pinfunction "I0_1") (pintype "input"))
    )
    (net (code "160") (name "~{IOT016}") (class "Default")
      (node (ref "EB5") (pin "5") (pinfunction "I1_5") (pintype "input"))
      (node (ref "EC1") (pin "12") (pinfunction "I0_12") (pintype "input"))
      (node (ref "EC3") (pin "9") (pinfunction "Y6_9") (pintype "output"))
    )
    (net (code "161") (name "~{IOT020}") (class "Default")
      (node (ref "EC2") (pin "15") (pinfunction "Y0_15") (pintype "output"))
      (node (ref "EC5") (pin "13") (pinfunction "CLR_13") (pintype "input"))
    )
    (net (code "162") (name "~{IO_PAUSE}") (class "Default")
      (node (ref "EC4") (pin "6") (pinfunction "I0_6") (pintype "input"))
      (node (ref "EC4") (pin "7") (pinfunction "I1_7") (pintype "input"))
      (node (ref "U$2") (pin "CD1") (pinfunction "1_CD1") (pintype "bidirectional"))
    )
    (net (code "163") (name "~{MD03}") (class "Default")
      (node (ref "ED3") (pin "9") (pinfunction "I0_9") (pintype "input"))
      (node (ref "U$2") (pin "AP1") (pinfunction "1_AP1") (pintype "bidirectional"))
    )
    (net (code "164") (name "~{MD04}") (class "Default")
      (node (ref "ED3") (pin "11") (pinfunction "I0_11") (pintype "input"))
      (node (ref "U$2") (pin "BK1") (pinfunction "1_BK1") (pintype "bidirectional"))
    )
    (net (code "165") (name "~{MD05}") (class "Default")
      (node (ref "ED3") (pin "5") (pinfunction "I1_5") (pintype "input"))
      (node (ref "U$2") (pin "BL1") (pinfunction "1_BL1") (pintype "bidirectional"))
    )
    (net (code "166") (name "~{MD06}") (class "Default")
      (node (ref "ED3") (pin "7") (pinfunction "I1_7") (pintype "input"))
      (node (ref "U$2") (pin "BM1") (pinfunction "1_BM1") (pintype "bidirectional"))
    )
    (net (code "167") (name "~{MD07}") (class "Default")
      (node (ref "EC4") (pin "10") (pinfunction "I1_10") (pintype "input"))
      (node (ref "U$2") (pin "BP1") (pinfunction "1_BP1") (pintype "bidirectional"))
    )
    (net (code "168") (name "~{MD08}") (class "Default")
      (node (ref "EC4") (pin "12") (pinfunction "I1_12") (pintype "input"))
      (node (ref "U$2") (pin "DK1") (pinfunction "1_DK1") (pintype "bidirectional"))
    )
    (net (code "169") (name "~{MD09}") (class "Default")
      (node (ref "ED2") (pin "7") (pinfunction "I1_7") (pintype "input"))
      (node (ref "U$2") (pin "DL1") (pinfunction "1_DL1") (pintype "bidirectional"))
    )
    (net (code "170") (name "~{MD10}") (class "Default")
      (node (ref "ED2") (pin "5") (pinfunction "I1_5") (pintype "input"))
      (node (ref "U$2") (pin "DM1") (pinfunction "1_DM1") (pintype "bidirectional"))
    )
    (net (code "171") (name "~{MD11}") (class "Default")
      (node (ref "ED2") (pin "9") (pinfunction "I0_9") (pintype "input"))
      (node (ref "U$2") (pin "DP1") (pinfunction "1_DP1") (pintype "bidirectional"))
    )
    (net (code "172") (name "~{PTSTROBE}") (class "Default")
      (node (ref "EA5") (pin "1") (pinfunction "A_1") (pintype "input"))
      (node (ref "EA6") (pin "2") (pinfunction "B_2") (pintype "input"))
      (node (ref "EB2") (pin "10") (pinfunction "O_10") (pintype "output"))
      (node (ref "EB6") (pin "12") (pinfunction "D_12") (pintype "input"))
      (node (ref "EB6") (pin "2") (pinfunction "D_2") (pintype "input"))
    )
    (net (code "173") (name "~{SKIP}") (class "Default")
      (node (ref "EC6") (pin "4") (pinfunction "O_4") (pintype "open_collector"))
      (node (ref "U$2") (pin "CS1") (pinfunction "1_CS1") (pintype "bidirectional"))
    )
    (net (code "174") (name "~{TP3}") (class "Default")
      (node (ref "EC4") (pin "3") (pinfunction "O_3") (pintype "output"))
      (node (ref "EC7") (pin "10") (pinfunction "I1_10") (pintype "input"))
      (node (ref "EC7") (pin "2") (pinfunction "I1_2") (pintype "input"))
      (node (ref "EC7") (pin "5") (pinfunction "I1_5") (pintype "input"))
      (node (ref "ED5") (pin "12") (pinfunction "I0_12") (pintype "input"))
      (node (ref "ED5") (pin "5") (pinfunction "I1_5") (pintype "input"))
      (node (ref "ED5") (pin "9") (pinfunction "I0_9") (pintype "input"))
    )
    (net (code "175") (name "~{TP3010}") (class "Default")
      (node (ref "ED5") (pin "8") (pinfunction "O_8") (pintype "output"))
      (node (ref "ED6") (pin "1") (pinfunction "I0_1") (pintype "input"))
    )
    (net (code "176") (name "~{TP3013}") (class "Default")
      (node (ref "EB7") (pin "1") (pinfunction "CLR_1") (pintype "input"))
      (node (ref "EC7") (pin "8") (pinfunction "O_8") (pintype "output"))
    )
    (net (code "177") (name "~{TP3015}") (class "Default")
      (node (ref "EB7") (pin "4") (pinfunction "PRE_4") (pintype "input"))
      (node (ref "EC7") (pin "3") (pinfunction "O_3") (pintype "output"))
    )
  )
)
